# converter.net
KiCad netlist of a schematic drawn in Altium Designer
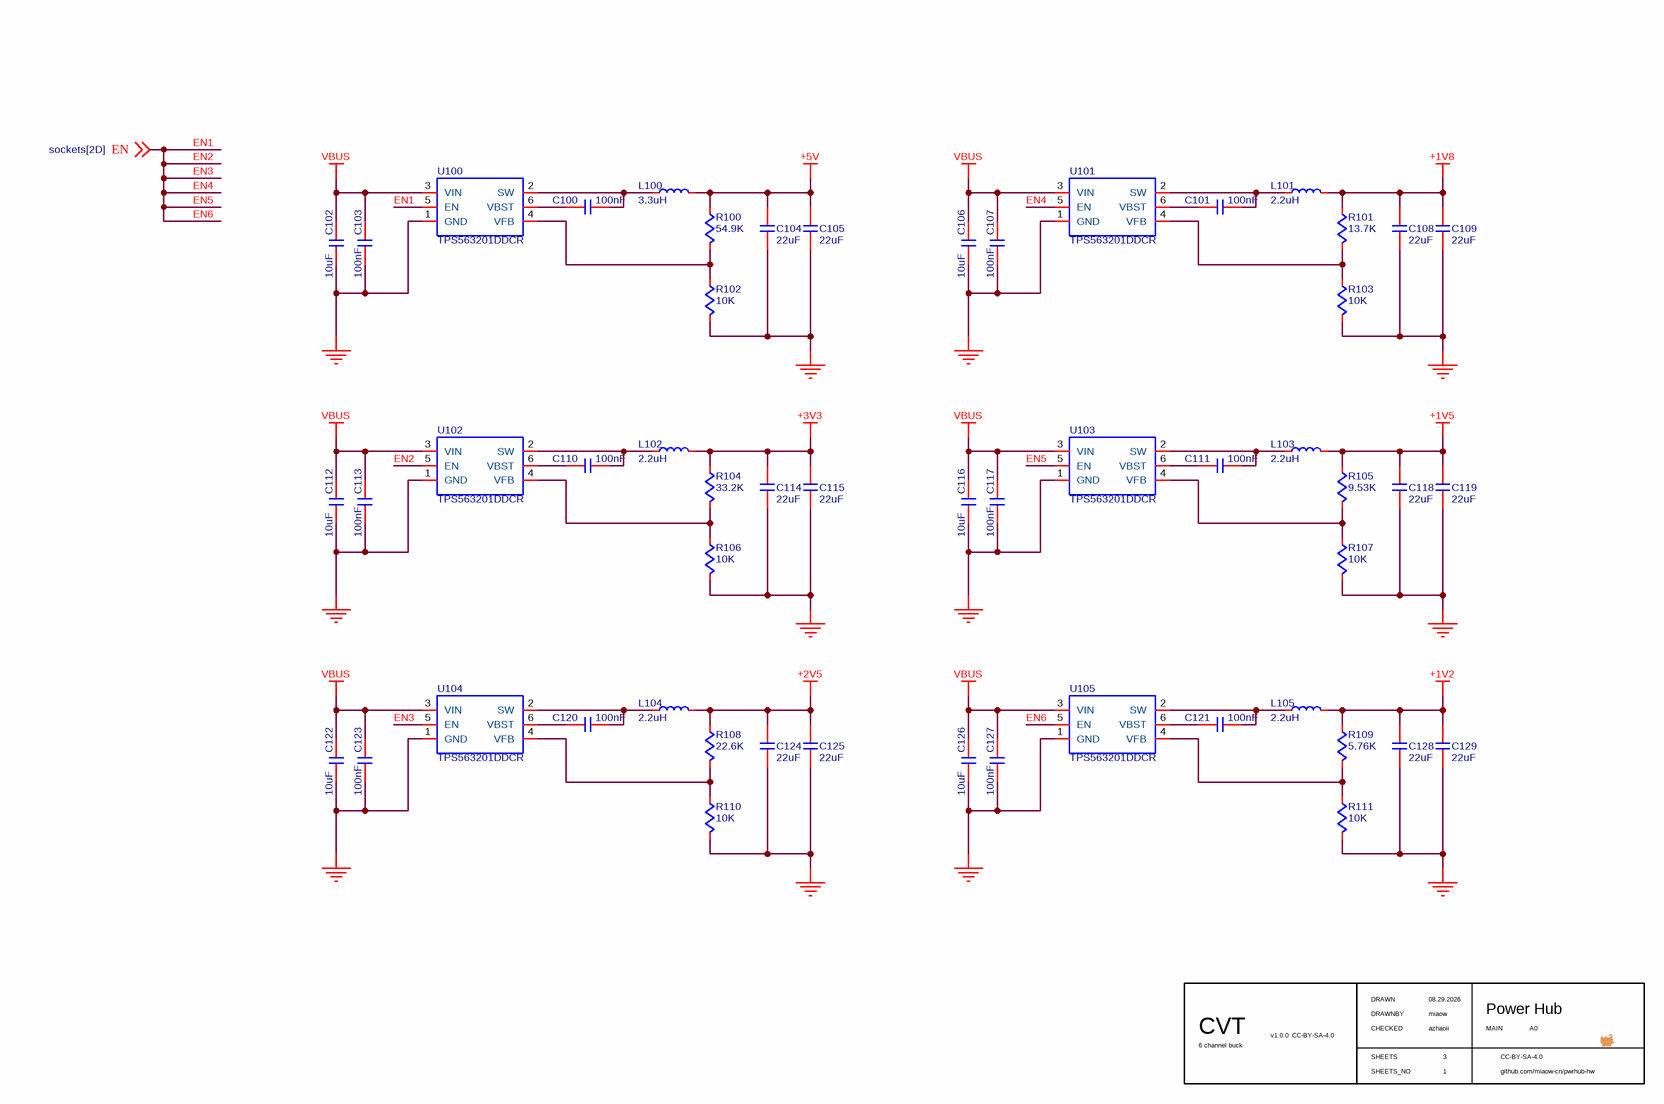
[diagram p0: converter.schdoc]

(export (version "E")
  (design (tool "Eeschema 10.0.6"))
  (components
    (comp (ref "C100")
      (value "100nF")
      (footprint "mw:C0402")
      (fields (field (name "VOLTAGE") "25V") (field (name "Comment") "C-NOMO"))
      (libsource (lib "mw") (part "C-NOMO"))
    )
    (comp (ref "C101")
      (value "100nF")
      (footprint "mw:C0402")
      (fields (field (name "VOLTAGE") "25V") (field (name "Comment") "C-NOMO"))
      (libsource (lib "mw") (part "C-NOMO"))
    )
    (comp (ref "C102")
      (value "10uF")
      (footprint "mw:C0805")
      (fields (field (name "VOLTAGE") "25V") (field (name "Comment") "C-NOMO"))
      (libsource (lib "mw") (part "C-NOMO"))
    )
    (comp (ref "C103")
      (value "100nF")
      (footprint "mw:C0402")
      (fields (field (name "VOLTAGE") "25V") (field (name "Comment") "C-NOMO"))
      (libsource (lib "mw") (part "C-NOMO"))
    )
    (comp (ref "C104")
      (value "22uF")
      (footprint "mw:C0805")
      (fields (field (name "VOLTAGE") "25V") (field (name "Comment") "C-NOMO"))
      (libsource (lib "mw") (part "C-NOMO"))
    )
    (comp (ref "C105")
      (value "22uF")
      (footprint "mw:C0805")
      (fields (field (name "VOLTAGE") "25V") (field (name "Comment") "C-NOMO"))
      (libsource (lib "mw") (part "C-NOMO"))
    )
    (comp (ref "C106")
      (value "10uF")
      (footprint "mw:C0805")
      (fields (field (name "VOLTAGE") "25V") (field (name "Comment") "C-NOMO"))
      (libsource (lib "mw") (part "C-NOMO"))
    )
    (comp (ref "C107")
      (value "100nF")
      (footprint "mw:C0402")
      (fields (field (name "VOLTAGE") "25V") (field (name "Comment") "C-NOMO"))
      (libsource (lib "mw") (part "C-NOMO"))
    )
    (comp (ref "C108")
      (value "22uF")
      (footprint "mw:C0805")
      (fields (field (name "VOLTAGE") "25V") (field (name "Comment") "C-NOMO"))
      (libsource (lib "mw") (part "C-NOMO"))
    )
    (comp (ref "C109")
      (value "22uF")
      (footprint "mw:C0805")
      (fields (field (name "VOLTAGE") "25V") (field (name "Comment") "C-NOMO"))
      (libsource (lib "mw") (part "C-NOMO"))
    )
    (comp (ref "C110")
      (value "100nF")
      (footprint "mw:C0402")
      (fields (field (name "VOLTAGE") "25V") (field (name "Comment") "C-NOMO"))
      (libsource (lib "mw") (part "C-NOMO"))
    )
    (comp (ref "C111")
      (value "100nF")
      (footprint "mw:C0402")
      (fields (field (name "VOLTAGE") "25V") (field (name "Comment") "C-NOMO"))
      (libsource (lib "mw") (part "C-NOMO"))
    )
    (comp (ref "C112")
      (value "10uF")
      (footprint "mw:C0805")
      (fields (field (name "VOLTAGE") "25V") (field (name "Comment") "C-NOMO"))
      (libsource (lib "mw") (part "C-NOMO"))
    )
    (comp (ref "C113")
      (value "100nF")
      (footprint "mw:C0402")
      (fields (field (name "VOLTAGE") "25V") (field (name "Comment") "C-NOMO"))
      (libsource (lib "mw") (part "C-NOMO"))
    )
    (comp (ref "C114")
      (value "22uF")
      (footprint "mw:C0805")
      (fields (field (name "VOLTAGE") "25V") (field (name "Comment") "C-NOMO"))
      (libsource (lib "mw") (part "C-NOMO"))
    )
    (comp (ref "C115")
      (value "22uF")
      (footprint "mw:C0805")
      (fields (field (name "VOLTAGE") "25V") (field (name "Comment") "C-NOMO"))
      (libsource (lib "mw") (part "C-NOMO"))
    )
    (comp (ref "C116")
      (value "10uF")
      (footprint "mw:C0805")
      (fields (field (name "VOLTAGE") "25V") (field (name "Comment") "C-NOMO"))
      (libsource (lib "mw") (part "C-NOMO"))
    )
    (comp (ref "C117")
      (value "100nF")
      (footprint "mw:C0402")
      (fields (field (name "VOLTAGE") "25V") (field (name "Comment") "C-NOMO"))
      (libsource (lib "mw") (part "C-NOMO"))
    )
    (comp (ref "C118")
      (value "22uF")
      (footprint "mw:C0805")
      (fields (field (name "VOLTAGE") "25V") (field (name "Comment") "C-NOMO"))
      (libsource (lib "mw") (part "C-NOMO"))
    )
    (comp (ref "C119")
      (value "22uF")
      (footprint "mw:C0805")
      (fields (field (name "VOLTAGE") "25V") (field (name "Comment") "C-NOMO"))
      (libsource (lib "mw") (part "C-NOMO"))
    )
    (comp (ref "C120")
      (value "100nF")
      (footprint "mw:C0402")
      (fields (field (name "VOLTAGE") "25V") (field (name "Comment") "C-NOMO"))
      (libsource (lib "mw") (part "C-NOMO"))
    )
    (comp (ref "C121")
      (value "100nF")
      (footprint "mw:C0402")
      (fields (field (name "VOLTAGE") "25V") (field (name "Comment") "C-NOMO"))
      (libsource (lib "mw") (part "C-NOMO"))
    )
    (comp (ref "C122")
      (value "10uF")
      (footprint "mw:C0805")
      (fields (field (name "VOLTAGE") "25V") (field (name "Comment") "C-NOMO"))
      (libsource (lib "mw") (part "C-NOMO"))
    )
    (comp (ref "C123")
      (value "100nF")
      (footprint "mw:C0402")
      (fields (field (name "VOLTAGE") "25V") (field (name "Comment") "C-NOMO"))
      (libsource (lib "mw") (part "C-NOMO"))
    )
    (comp (ref "C124")
      (value "22uF")
      (footprint "mw:C0805")
      (fields (field (name "VOLTAGE") "25V") (field (name "Comment") "C-NOMO"))
      (libsource (lib "mw") (part "C-NOMO"))
    )
    (comp (ref "C125")
      (value "22uF")
      (footprint "mw:C0805")
      (fields (field (name "VOLTAGE") "25V") (field (name "Comment") "C-NOMO"))
      (libsource (lib "mw") (part "C-NOMO"))
    )
    (comp (ref "C126")
      (value "10uF")
      (footprint "mw:C0805")
      (fields (field (name "VOLTAGE") "25V") (field (name "Comment") "C-NOMO"))
      (libsource (lib "mw") (part "C-NOMO"))
    )
    (comp (ref "C127")
      (value "100nF")
      (footprint "mw:C0402")
      (fields (field (name "VOLTAGE") "25V") (field (name "Comment") "C-NOMO"))
      (libsource (lib "mw") (part "C-NOMO"))
    )
    (comp (ref "C128")
      (value "22uF")
      (footprint "mw:C0805")
      (fields (field (name "VOLTAGE") "25V") (field (name "Comment") "C-NOMO"))
      (libsource (lib "mw") (part "C-NOMO"))
    )
    (comp (ref "C129")
      (value "22uF")
      (footprint "mw:C0805")
      (fields (field (name "VOLTAGE") "25V") (field (name "Comment") "C-NOMO"))
      (libsource (lib "mw") (part "C-NOMO"))
    )
    (comp (ref "L100")
      (value "3.3uH")
      (footprint "mw:FXL0530")
      (fields (field (name "Comment") "L") (field (name "PUBLISHER") "Altium Limited"))
      (libsource (lib "mw") (part "L"))
    )
    (comp (ref "L101")
      (value "2.2uH")
      (footprint "mw:FXL0420")
      (fields (field (name "Comment") "L") (field (name "PUBLISHER") "Altium Limited"))
      (libsource (lib "mw") (part "L"))
    )
    (comp (ref "L102")
      (value "2.2uH")
      (footprint "mw:FXL0420")
      (fields (field (name "Comment") "L") (field (name "PUBLISHER") "Altium Limited"))
      (libsource (lib "mw") (part "L"))
    )
    (comp (ref "L103")
      (value "2.2uH")
      (footprint "mw:FXL0420")
      (fields (field (name "Comment") "L") (field (name "PUBLISHER") "Altium Limited"))
      (libsource (lib "mw") (part "L"))
    )
    (comp (ref "L104")
      (value "2.2uH")
      (footprint "mw:FXL0420")
      (fields (field (name "Comment") "L") (field (name "PUBLISHER") "Altium Limited"))
      (libsource (lib "mw") (part "L"))
    )
    (comp (ref "L105")
      (value "2.2uH")
      (footprint "mw:FXL0420")
      (fields (field (name "Comment") "L") (field (name "PUBLISHER") "Altium Limited"))
      (libsource (lib "mw") (part "L"))
    )
    (comp (ref "R100")
      (value "54.9K")
      (footprint "mw:R0402")
      (fields (field (name "Comment") "R"))
      (libsource (lib "mw") (part "R"))
    )
    (comp (ref "R101")
      (value "13.7K")
      (footprint "mw:R0402")
      (fields (field (name "Comment") "R"))
      (libsource (lib "mw") (part "R"))
    )
    (comp (ref "R102")
      (value "10K")
      (footprint "mw:R0402")
      (fields (field (name "Comment") "R"))
      (libsource (lib "mw") (part "R"))
    )
    (comp (ref "R103")
      (value "10K")
      (footprint "mw:R0402")
      (fields (field (name "Comment") "R"))
      (libsource (lib "mw") (part "R"))
    )
    (comp (ref "R104")
      (value "33.2K")
      (footprint "mw:R0402")
      (fields (field (name "Comment") "R"))
      (libsource (lib "mw") (part "R"))
    )
    (comp (ref "R105")
      (value "9.53K")
      (footprint "mw:R0402")
      (fields (field (name "Comment") "R"))
      (libsource (lib "mw") (part "R"))
    )
    (comp (ref "R106")
      (value "10K")
      (footprint "mw:R0402")
      (fields (field (name "Comment") "R"))
      (libsource (lib "mw") (part "R"))
    )
    (comp (ref "R107")
      (value "10K")
      (footprint "mw:R0402")
      (fields (field (name "Comment") "R"))
      (libsource (lib "mw") (part "R"))
    )
    (comp (ref "R108")
      (value "22.6K")
      (footprint "mw:R0402")
      (fields (field (name "Comment") "R"))
      (libsource (lib "mw") (part "R"))
    )
    (comp (ref "R109")
      (value "5.76K")
      (footprint "mw:R0402")
      (fields (field (name "Comment") "R"))
      (libsource (lib "mw") (part "R"))
    )
    (comp (ref "R110")
      (value "10K")
      (footprint "mw:R0402")
      (fields (field (name "Comment") "R"))
      (libsource (lib "mw") (part "R"))
    )
    (comp (ref "R111")
      (value "10K")
      (footprint "mw:R0402")
      (fields (field (name "Comment") "R"))
      (libsource (lib "mw") (part "R"))
    )
    (comp (ref "U100")
      (value "TPS563201DDCR")
      (footprint "mw:TPS563201DDCR")
      (description "BUCK")
      (libsource (lib "mw") (part "TPS563201DDCR"))
    )
    (comp (ref "U101")
      (value "TPS563201DDCR")
      (footprint "mw:TPS563201DDCR")
      (description "BUCK")
      (libsource (lib "mw") (part "TPS563201DDCR"))
    )
    (comp (ref "U102")
      (value "TPS563201DDCR")
      (footprint "mw:TPS563201DDCR")
      (description "BUCK")
      (libsource (lib "mw") (part "TPS563201DDCR"))
    )
    (comp (ref "U103")
      (value "TPS563201DDCR")
      (footprint "mw:TPS563201DDCR")
      (description "BUCK")
      (libsource (lib "mw") (part "TPS563201DDCR"))
    )
    (comp (ref "U104")
      (value "TPS563201DDCR")
      (footprint "mw:TPS563201DDCR")
      (description "BUCK")
      (libsource (lib "mw") (part "TPS563201DDCR"))
    )
    (comp (ref "U105")
      (value "TPS563201DDCR")
      (footprint "mw:TPS563201DDCR")
      (description "BUCK")
      (libsource (lib "mw") (part "TPS563201DDCR"))
    )
  )
  (nets
    (net (code "1") (name "+1V2") (class "Default")
      (node (ref "C128") (pin "2") (pinfunction "2_2") (pintype "passive"))
      (node (ref "C129") (pin "2") (pinfunction "2_2") (pintype "passive"))
      (node (ref "L105") (pin "2") (pinfunction "2_2") (pintype "passive"))
      (node (ref "R109") (pin "2") (pinfunction "2_2") (pintype "passive"))
    )
    (net (code "2") (name "+1V5") (class "Default")
      (node (ref "C118") (pin "2") (pinfunction "2_2") (pintype "passive"))
      (node (ref "C119") (pin "2") (pinfunction "2_2") (pintype "passive"))
      (node (ref "L103") (pin "2") (pinfunction "2_2") (pintype "passive"))
      (node (ref "R105") (pin "2") (pinfunction "2_2") (pintype "passive"))
    )
    (net (code "3") (name "+1V8") (class "Default")
      (node (ref "C108") (pin "2") (pinfunction "2_2") (pintype "passive"))
      (node (ref "C109") (pin "2") (pinfunction "2_2") (pintype "passive"))
      (node (ref "L101") (pin "2") (pinfunction "2_2") (pintype "passive"))
      (node (ref "R101") (pin "2") (pinfunction "2_2") (pintype "passive"))
    )
    (net (code "4") (name "+2V5") (class "Default")
      (node (ref "C124") (pin "2") (pinfunction "2_2") (pintype "passive"))
      (node (ref "C125") (pin "2") (pinfunction "2_2") (pintype "passive"))
      (node (ref "L104") (pin "2") (pinfunction "2_2") (pintype "passive"))
      (node (ref "R108") (pin "2") (pinfunction "2_2") (pintype "passive"))
    )
    (net (code "5") (name "+3V3") (class "Default")
      (node (ref "C114") (pin "2") (pinfunction "2_2") (pintype "passive"))
      (node (ref "C115") (pin "2") (pinfunction "2_2") (pintype "passive"))
      (node (ref "L102") (pin "2") (pinfunction "2_2") (pintype "passive"))
      (node (ref "R104") (pin "2") (pinfunction "2_2") (pintype "passive"))
    )
    (net (code "6") (name "+5V") (class "Default")
      (node (ref "C104") (pin "2") (pinfunction "2_2") (pintype "passive"))
      (node (ref "C105") (pin "2") (pinfunction "2_2") (pintype "passive"))
      (node (ref "L100") (pin "2") (pinfunction "2_2") (pintype "passive"))
      (node (ref "R100") (pin "2") (pinfunction "2_2") (pintype "passive"))
    )
    (net (code "7") (name "EN") (class "Default")
      (node (ref "U100") (pin "5") (pinfunction "EN_5") (pintype "passive"))
      (node (ref "U101") (pin "5") (pinfunction "EN_5") (pintype "passive"))
      (node (ref "U102") (pin "5") (pinfunction "EN_5") (pintype "passive"))
      (node (ref "U103") (pin "5") (pinfunction "EN_5") (pintype "passive"))
      (node (ref "U104") (pin "5") (pinfunction "EN_5") (pintype "passive"))
      (node (ref "U105") (pin "5") (pinfunction "EN_5") (pintype "passive"))
    )
    (net (code "8") (name "GND") (class "Default")
      (node (ref "C102") (pin "1") (pinfunction "1_1") (pintype "passive"))
      (node (ref "C103") (pin "1") (pinfunction "1_1") (pintype "passive"))
      (node (ref "C104") (pin "1") (pinfunction "1_1") (pintype "passive"))
      (node (ref "C105") (pin "1") (pinfunction "1_1") (pintype "passive"))
      (node (ref "C106") (pin "1") (pinfunction "1_1") (pintype "passive"))
      (node (ref "C107") (pin "1") (pinfunction "1_1") (pintype "passive"))
      (node (ref "C108") (pin "1") (pinfunction "1_1") (pintype "passive"))
      (node (ref "C109") (pin "1") (pinfunction "1_1") (pintype "passive"))
      (node (ref "C112") (pin "1") (pinfunction "1_1") (pintype "passive"))
      (node (ref "C113") (pin "1") (pinfunction "1_1") (pintype "passive"))
      (node (ref "C114") (pin "1") (pinfunction "1_1") (pintype "passive"))
      (node (ref "C115") (pin "1") (pinfunction "1_1") (pintype "passive"))
      (node (ref "C116") (pin "1") (pinfunction "1_1") (pintype "passive"))
      (node (ref "C117") (pin "1") (pinfunction "1_1") (pintype "passive"))
      (node (ref "C118") (pin "1") (pinfunction "1_1") (pintype "passive"))
      (node (ref "C119") (pin "1") (pinfunction "1_1") (pintype "passive"))
      (node (ref "C122") (pin "1") (pinfunction "1_1") (pintype "passive"))
      (node (ref "C123") (pin "1") (pinfunction "1_1") (pintype "passive"))
      (node (ref "C124") (pin "1") (pinfunction "1_1") (pintype "passive"))
      (node (ref "C125") (pin "1") (pinfunction "1_1") (pintype "passive"))
      (node (ref "C126") (pin "1") (pinfunction "1_1") (pintype "passive"))
      (node (ref "C127") (pin "1") (pinfunction "1_1") (pintype "passive"))
      (node (ref "C128") (pin "1") (pinfunction "1_1") (pintype "passive"))
      (node (ref "C129") (pin "1") (pinfunction "1_1") (pintype "passive"))
      (node (ref "R102") (pin "1") (pinfunction "1_1") (pintype "passive"))
      (node (ref "R103") (pin "1") (pinfunction "1_1") (pintype "passive"))
      (node (ref "R106") (pin "1") (pinfunction "1_1") (pintype "passive"))
      (node (ref "R107") (pin "1") (pinfunction "1_1") (pintype "passive"))
      (node (ref "R110") (pin "1") (pinfunction "1_1") (pintype "passive"))
      (node (ref "R111") (pin "1") (pinfunction "1_1") (pintype "passive"))
      (node (ref "U100") (pin "1") (pinfunction "GND_1") (pintype "passive"))
      (node (ref "U101") (pin "1") (pinfunction "GND_1") (pintype "passive"))
      (node (ref "U102") (pin "1") (pinfunction "GND_1") (pintype "passive"))
      (node (ref "U103") (pin "1") (pinfunction "GND_1") (pintype "passive"))
      (node (ref "U104") (pin "1") (pinfunction "GND_1") (pintype "passive"))
      (node (ref "U105") (pin "1") (pinfunction "GND_1") (pintype "passive"))
    )
    (net (code "9") (name "Net-(U100-SW)") (class "Default")
      (node (ref "C100") (pin "2") (pinfunction "2_2") (pintype "passive"))
      (node (ref "L100") (pin "1") (pinfunction "1_1") (pintype "passive"))
      (node (ref "U100") (pin "2") (pinfunction "SW_2") (pintype "passive"))
    )
    (net (code "10") (name "Net-(U100-VBST)") (class "Default")
      (node (ref "C100") (pin "1") (pinfunction "1_1") (pintype "passive"))
      (node (ref "U100") (pin "6") (pinfunction "VBST_6") (pintype "passive"))
    )
    (net (code "11") (name "Net-(U100-VFB)") (class "Default")
      (node (ref "R100") (pin "1") (pinfunction "1_1") (pintype "passive"))
      (node (ref "R102") (pin "2") (pinfunction "2_2") (pintype "passive"))
      (node (ref "U100") (pin "4") (pinfunction "VFB_4") (pintype "passive"))
    )
    (net (code "12") (name "Net-(U101-SW)") (class "Default")
      (node (ref "C101") (pin "2") (pinfunction "2_2") (pintype "passive"))
      (node (ref "L101") (pin "1") (pinfunction "1_1") (pintype "passive"))
      (node (ref "U101") (pin "2") (pinfunction "SW_2") (pintype "passive"))
    )
    (net (code "13") (name "Net-(U101-VBST)") (class "Default")
      (node (ref "C101") (pin "1") (pinfunction "1_1") (pintype "passive"))
      (node (ref "U101") (pin "6") (pinfunction "VBST_6") (pintype "passive"))
    )
    (net (code "14") (name "Net-(U101-VFB)") (class "Default")
      (node (ref "R101") (pin "1") (pinfunction "1_1") (pintype "passive"))
      (node (ref "R103") (pin "2") (pinfunction "2_2") (pintype "passive"))
      (node (ref "U101") (pin "4") (pinfunction "VFB_4") (pintype "passive"))
    )
    (net (code "15") (name "Net-(U102-SW)") (class "Default")
      (node (ref "C110") (pin "2") (pinfunction "2_2") (pintype "passive"))
      (node (ref "L102") (pin "1") (pinfunction "1_1") (pintype "passive"))
      (node (ref "U102") (pin "2") (pinfunction "SW_2") (pintype "passive"))
    )
    (net (code "16") (name "Net-(U102-VBST)") (class "Default")
      (node (ref "C110") (pin "1") (pinfunction "1_1") (pintype "passive"))
      (node (ref "U102") (pin "6") (pinfunction "VBST_6") (pintype "passive"))
    )
    (net (code "17") (name "Net-(U102-VFB)") (class "Default")
      (node (ref "R104") (pin "1") (pinfunction "1_1") (pintype "passive"))
      (node (ref "R106") (pin "2") (pinfunction "2_2") (pintype "passive"))
      (node (ref "U102") (pin "4") (pinfunction "VFB_4") (pintype "passive"))
    )
    (net (code "18") (name "Net-(U103-SW)") (class "Default")
      (node (ref "C111") (pin "2") (pinfunction "2_2") (pintype "passive"))
      (node (ref "L103") (pin "1") (pinfunction "1_1") (pintype "passive"))
      (node (ref "U103") (pin "2") (pinfunction "SW_2") (pintype "passive"))
    )
    (net (code "19") (name "Net-(U103-VBST)") (class "Default")
      (node (ref "C111") (pin "1") (pinfunction "1_1") (pintype "passive"))
      (node (ref "U103") (pin "6") (pinfunction "VBST_6") (pintype "passive"))
    )
    (net (code "20") (name "Net-(U103-VFB)") (class "Default")
      (node (ref "R105") (pin "1") (pinfunction "1_1") (pintype "passive"))
      (node (ref "R107") (pin "2") (pinfunction "2_2") (pintype "passive"))
      (node (ref "U103") (pin "4") (pinfunction "VFB_4") (pintype "passive"))
    )
    (net (code "21") (name "Net-(U104-SW)") (class "Default")
      (node (ref "C120") (pin "2") (pinfunction "2_2") (pintype "passive"))
      (node (ref "L104") (pin "1") (pinfunction "1_1") (pintype "passive"))
      (node (ref "U104") (pin "2") (pinfunction "SW_2") (pintype "passive"))
    )
    (net (code "22") (name "Net-(U104-VBST)") (class "Default")
      (node (ref "C120") (pin "1") (pinfunction "1_1") (pintype "passive"))
      (node (ref "U104") (pin "6") (pinfunction "VBST_6") (pintype "passive"))
    )
    (net (code "23") (name "Net-(U104-VFB)") (class "Default")
      (node (ref "R108") (pin "1") (pinfunction "1_1") (pintype "passive"))
      (node (ref "R110") (pin "2") (pinfunction "2_2") (pintype "passive"))
      (node (ref "U104") (pin "4") (pinfunction "VFB_4") (pintype "passive"))
    )
    (net (code "24") (name "Net-(U105-SW)") (class "Default")
      (node (ref "C121") (pin "2") (pinfunction "2_2") (pintype "passive"))
      (node (ref "L105") (pin "1") (pinfunction "1_1") (pintype "passive"))
      (node (ref "U105") (pin "2") (pinfunction "SW_2") (pintype "passive"))
    )
    (net (code "25") (name "Net-(U105-VBST)") (class "Default")
      (node (ref "C121") (pin "1") (pinfunction "1_1") (pintype "passive"))
      (node (ref "U105") (pin "6") (pinfunction "VBST_6") (pintype "passive"))
    )
    (net (code "26") (name "Net-(U105-VFB)") (class "Default")
      (node (ref "R109") (pin "1") (pinfunction "1_1") (pintype "passive"))
      (node (ref "R111") (pin "2") (pinfunction "2_2") (pintype "passive"))
      (node (ref "U105") (pin "4") (pinfunction "VFB_4") (pintype "passive"))
    )
    (net (code "27") (name "VBUS") (class "Default")
      (node (ref "C102") (pin "2") (pinfunction "2_2") (pintype "passive"))
      (node (ref "C103") (pin "2") (pinfunction "2_2") (pintype "passive"))
      (node (ref "C106") (pin "2") (pinfunction "2_2") (pintype "passive"))
      (node (ref "C107") (pin "2") (pinfunction "2_2") (pintype "passive"))
      (node (ref "C112") (pin "2") (pinfunction "2_2") (pintype "passive"))
      (node (ref "C113") (pin "2") (pinfunction "2_2") (pintype "passive"))
      (node (ref "C116") (pin "2") (pinfunction "2_2") (pintype "passive"))
      (node (ref "C117") (pin "2") (pinfunction "2_2") (pintype "passive"))
      (node (ref "C122") (pin "2") (pinfunction "2_2") (pintype "passive"))
      (node (ref "C123") (pin "2") (pinfunction "2_2") (pintype "passive"))
      (node (ref "C126") (pin "2") (pinfunction "2_2") (pintype "passive"))
      (node (ref "C127") (pin "2") (pinfunction "2_2") (pintype "passive"))
      (node (ref "U100") (pin "3") (pinfunction "VIN_3") (pintype "passive"))
      (node (ref "U101") (pin "3") (pinfunction "VIN_3") (pintype "passive"))
      (node (ref "U102") (pin "3") (pinfunction "VIN_3") (pintype "passive"))
      (node (ref "U103") (pin "3") (pinfunction "VIN_3") (pintype "passive"))
      (node (ref "U104") (pin "3") (pinfunction "VIN_3") (pintype "passive"))
      (node (ref "U105") (pin "3") (pinfunction "VIN_3") (pintype "passive"))
    )
  )
)
